# bela_expansion_card_3.net
KiCad netlist of a schematic drawn in Altium Designer
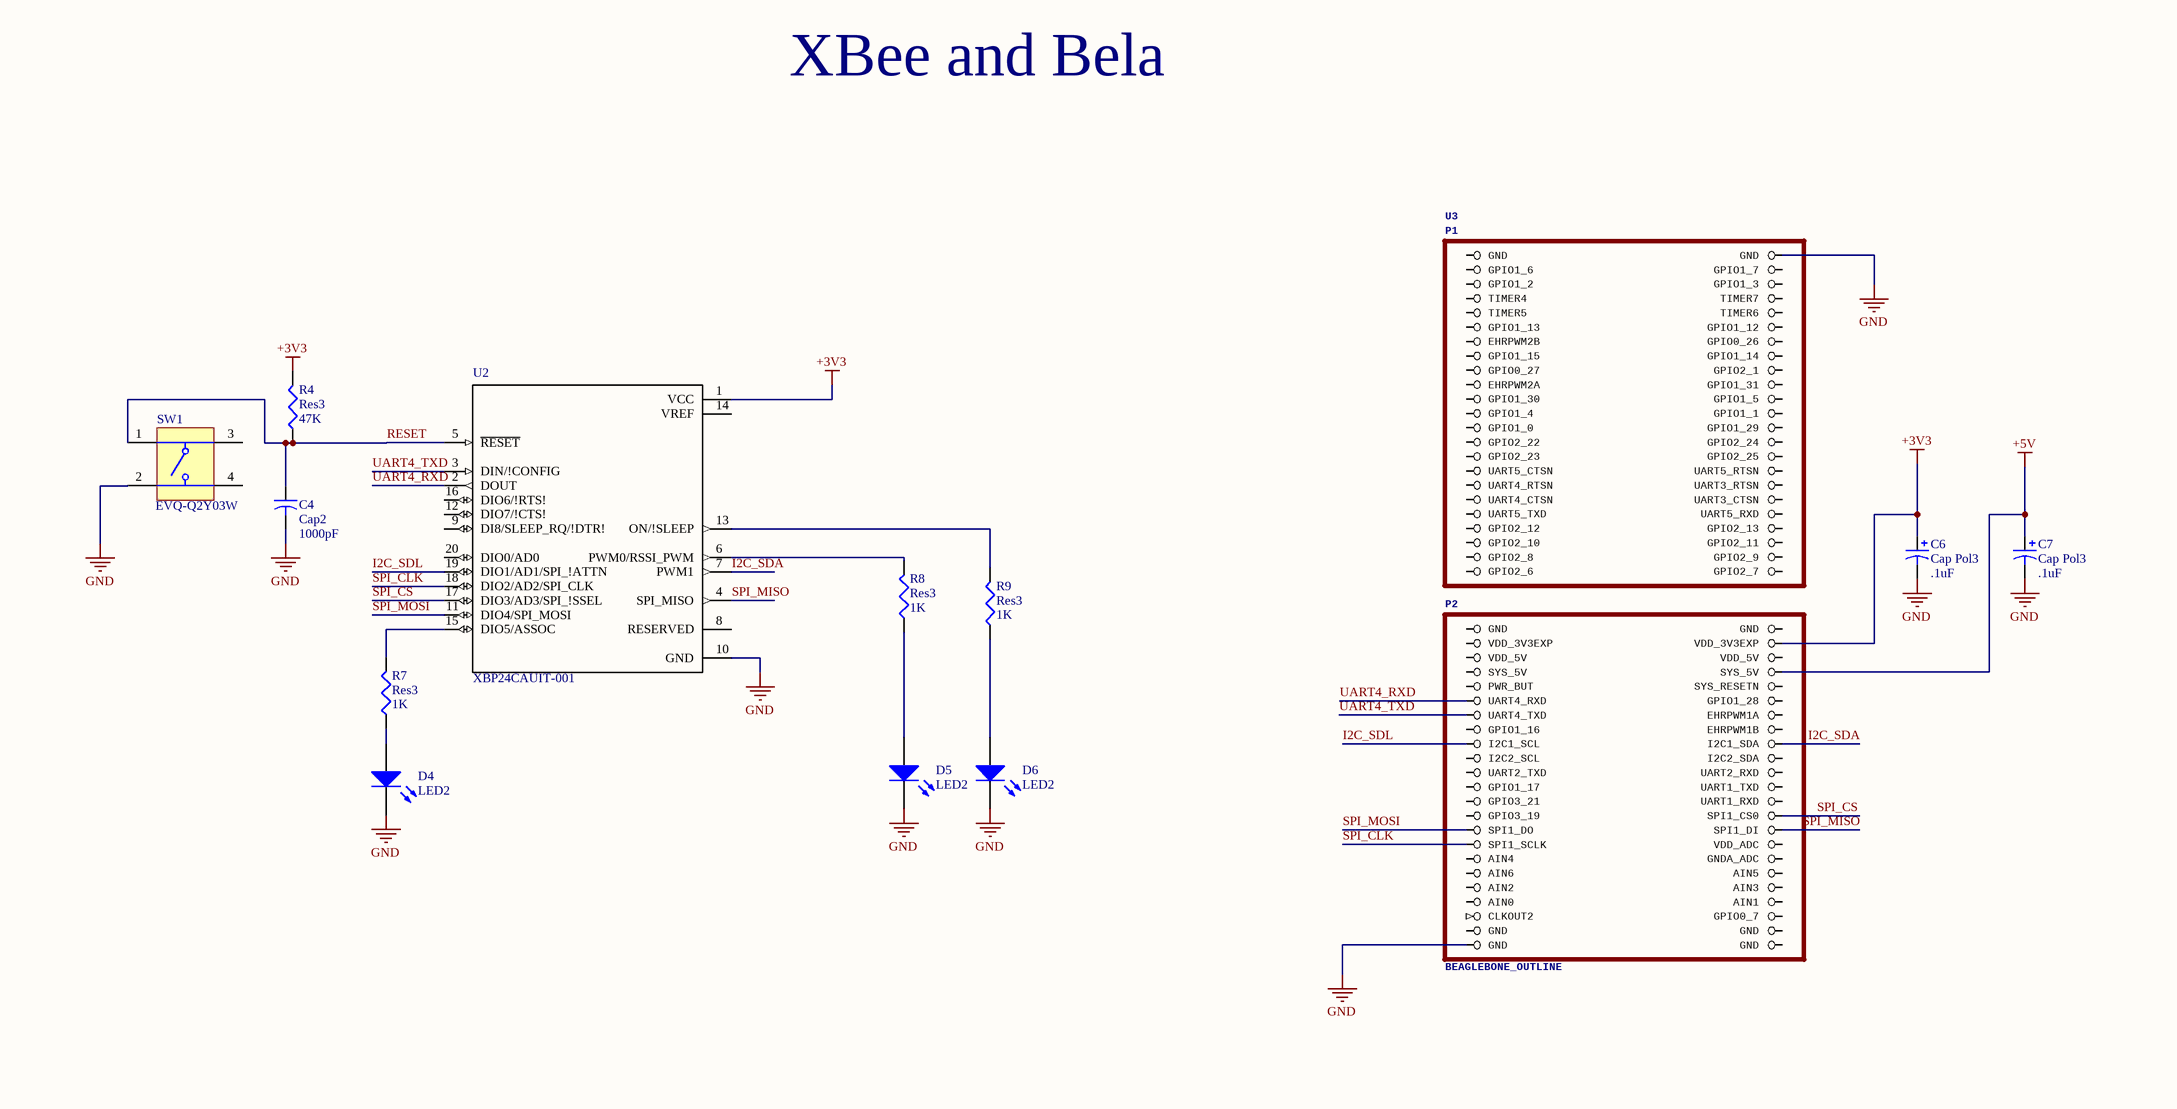
[diagram p0: bela_expansion_card_3.SchDoc]

(export (version "E")
  (design (tool "Eeschema 10.0.6"))
  (components
    (comp (ref "C4")
      (value "Cap2")
      (footprint "C0805")
      (description "Capacitor")
      (fields (field (name "ALTIUM_VALUE") "1000pF") (field (name "PUBLISHER") "Altium Limited"))
      (libsource (lib "EE_Emerge_SkillsProject") (part "Cap2_4"))
    )
    (comp (ref "C6")
      (value "Cap Pol3")
      (footprint "C0805")
      (description "Polarized Capacitor (Surface Mount)")
      (fields (field (name "ALTIUM_VALUE") ".1uF") (field (name "PUBLISHER") "Altium Limited"))
      (libsource (lib "Miscellaneous Devices") (part "Cap Pol3"))
    )
    (comp (ref "C7")
      (value "Cap Pol3")
      (footprint "C0805")
      (description "Polarized Capacitor (Surface Mount)")
      (fields (field (name "ALTIUM_VALUE") ".1uF") (field (name "PUBLISHER") "Altium Limited"))
      (libsource (lib "Miscellaneous Devices") (part "Cap Pol3"))
    )
    (comp (ref "D4")
      (value "LED2")
      (footprint "3.2X1.6X1.1")
      (description "Typical RED, GREEN, YELLOW, AMBER GaAs LED")
      (fields (field (name "PUBLISHER") "Altium Limited"))
      (libsource (lib "Miscellaneous Devices") (part "LED2"))
    )
    (comp (ref "D5")
      (value "LED2")
      (footprint "3.2X1.6X1.1")
      (description "Typical RED, GREEN, YELLOW, AMBER GaAs LED")
      (fields (field (name "PUBLISHER") "Altium Limited"))
      (libsource (lib "Miscellaneous Devices") (part "LED2"))
    )
    (comp (ref "D6")
      (value "LED2")
      (footprint "3.2X1.6X1.1")
      (description "Typical RED, GREEN, YELLOW, AMBER GaAs LED")
      (fields (field (name "PUBLISHER") "Altium Limited"))
      (libsource (lib "Miscellaneous Devices") (part "LED2"))
    )
    (comp (ref "R4")
      (value "Res3")
      (footprint "6-0805_L")
      (description "Resistor")
      (fields (field (name "ALTIUM_VALUE") "47K") (field (name "PUBLISHER") "Altium Limited"))
      (libsource (lib "Miscellaneous Devices") (part "Res3"))
    )
    (comp (ref "R7")
      (value "Res3")
      (footprint "6-0805_L")
      (description "Resistor")
      (fields (field (name "ALTIUM_VALUE") "1K") (field (name "PUBLISHER") "Altium Limited"))
      (libsource (lib "Miscellaneous Devices") (part "Res3"))
    )
    (comp (ref "R8")
      (value "Res3")
      (footprint "6-0805_L")
      (description "Resistor")
      (fields (field (name "ALTIUM_VALUE") "1K") (field (name "PUBLISHER") "Altium Limited"))
      (libsource (lib "Miscellaneous Devices") (part "Res3"))
    )
    (comp (ref "R9")
      (value "Res3")
      (footprint "6-0805_L")
      (description "Resistor")
      (fields (field (name "ALTIUM_VALUE") "1K") (field (name "PUBLISHER") "Altium Limited"))
      (libsource (lib "Miscellaneous Devices") (part "Res3"))
    )
    (comp (ref "SW1")
      (value "EVQ-Q2Y03W")
      (footprint "PNSC-EVQQ2_V")
      (description "Light Touch Switche, 3.5 N Force, Height 3.1 mm, -40 to 85 degC, 4-Pin SMD, RoHS, Tape and Reel")
      (fields (field (name "MANUFACTURER") "Panasonic"))
      (libsource (lib "Altium Content Vault") (part "SW-SPST-4"))
    )
    (comp (ref "U2")
      (value "XBP24CAUIT-001")
      (footprint "*MODULE_XBP24CAUIT-001")
      (description "802.15.4 Transceiver Module 2.4GHz Antenna Not Included, U.FL Through Hole")
      (fields (field (name "MF") "Digi International"))
      (libsource (lib "XBP24CAUIT-001") (part "XBP24CAUIT-001"))
    )
    (comp (ref "U3")
      (value "BEAGLEBONE_OUTLINE")
      (footprint "BEAGLEBONE_SHIELD")
      (description "Should match A3 pinout - but not completely tested")
      (fields (field (name "P1") "P1") (field (name "P2") "P2"))
      (libsource (lib "adafruit") (part "BEAGLEBONE_OUTLINE"))
    )
  )
  (nets
    (net (code "1") (name "+3V3") (class "Default")
      (node (ref "C6") (pin "1") (pinfunction "1_1") (pintype "passive"))
      (node (ref "R4") (pin "2") (pinfunction "2_2") (pintype "passive"))
      (node (ref "U2") (pin "1") (pinfunction "VCC_1") (pintype "power_in"))
      (node (ref "U3") (pin "50") (pinfunction "VDD_3V3EXP_50") (pintype "power_in"))
    )
    (net (code "2") (name "+5V") (class "Default")
      (node (ref "C7") (pin "1") (pinfunction "1_1") (pintype "passive"))
      (node (ref "U3") (pin "54") (pinfunction "SYS_5V_54") (pintype "passive"))
    )
    (net (code "3") (name "/I2C_SDA") (class "Default")
      (node (ref "U2") (pin "7") (pinfunction "PWM1_7") (pintype "output"))
      (node (ref "U3") (pin "64") (pinfunction "I2C1_SDA_64") (pintype "passive"))
    )
    (net (code "4") (name "/I2C_SDL") (class "Default")
      (node (ref "U2") (pin "19") (pinfunction "DIO1/AD1/SPI_!ATTN_19") (pintype "bidirectional"))
      (node (ref "U3") (pin "63") (pinfunction "I2C1_SCL_63") (pintype "passive"))
    )
    (net (code "5") (name "/RESET") (class "Default")
      (node (ref "C4") (pin "1") (pinfunction "1_1") (pintype "passive"))
      (node (ref "R4") (pin "1") (pinfunction "1_1") (pintype "passive"))
      (node (ref "SW1") (pin "1") (pinfunction "A_1") (pintype "passive"))
      (node (ref "U2") (pin "5") (pinfunction "~{RESET}_5") (pintype "input"))
    )
    (net (code "6") (name "/SPI_CLK") (class "Default")
      (node (ref "U2") (pin "18") (pinfunction "DIO2/AD2/SPI_CLK_18") (pintype "bidirectional"))
      (node (ref "U3") (pin "77") (pinfunction "SPI1_SCLK_77") (pintype "passive"))
    )
    (net (code "7") (name "/SPI_CS") (class "Default")
      (node (ref "U2") (pin "17") (pinfunction "DIO3/AD3/SPI_!SSEL_17") (pintype "bidirectional"))
      (node (ref "U3") (pin "74") (pinfunction "SPI1_CS0_74") (pintype "passive"))
    )
    (net (code "8") (name "/SPI_MISO") (class "Default")
      (node (ref "U2") (pin "4") (pinfunction "SPI_MISO_4") (pintype "output"))
      (node (ref "U3") (pin "76") (pinfunction "SPI1_DI_76") (pintype "passive"))
    )
    (net (code "9") (name "/SPI_MOSI") (class "Default")
      (node (ref "U2") (pin "11") (pinfunction "DIO4/SPI_MOSI_11") (pintype "bidirectional"))
      (node (ref "U3") (pin "75") (pinfunction "SPI1_DO_75") (pintype "passive"))
    )
    (net (code "10") (name "/UART4_RXD") (class "Default")
      (node (ref "U2") (pin "2") (pinfunction "DOUT_2") (pintype "output"))
      (node (ref "U3") (pin "57") (pinfunction "UART4_RXD_57") (pintype "passive"))
    )
    (net (code "11") (name "/UART4_TXD") (class "Default")
      (node (ref "U2") (pin "3") (pinfunction "DIN/!CONFIG_3") (pintype "input"))
      (node (ref "U3") (pin "59") (pinfunction "UART4_TXD_59") (pintype "passive"))
    )
    (net (code "12") (name "GND") (class "Default")
      (node (ref "C4") (pin "2") (pinfunction "2_2") (pintype "passive"))
      (node (ref "C6") (pin "2") (pinfunction "2_2") (pintype "passive"))
      (node (ref "C7") (pin "2") (pinfunction "2_2") (pintype "passive"))
      (node (ref "D4") (pin "2") (pinfunction "K_2") (pintype "passive"))
      (node (ref "D5") (pin "2") (pinfunction "K_2") (pintype "passive"))
      (node (ref "D6") (pin "2") (pinfunction "K_2") (pintype "passive"))
      (node (ref "SW1") (pin "2") (pinfunction "B_2") (pintype "passive"))
      (node (ref "U2") (pin "10") (pinfunction "GND_10") (pintype "power_in"))
      (node (ref "U3") (pin "2") (pinfunction "GND_2") (pintype "power_in"))
      (node (ref "U3") (pin "91") (pinfunction "GND_91") (pintype "power_in"))
    )
    (net (code "13") (name "Net-(D4-A)") (class "Default")
      (node (ref "D4") (pin "1") (pinfunction "A_1") (pintype "passive"))
      (node (ref "R7") (pin "1") (pinfunction "1_1") (pintype "passive"))
    )
    (net (code "14") (name "Net-(D5-A)") (class "Default")
      (node (ref "D5") (pin "1") (pinfunction "A_1") (pintype "passive"))
      (node (ref "R8") (pin "1") (pinfunction "1_1") (pintype "passive"))
    )
    (net (code "15") (name "Net-(D6-A)") (class "Default")
      (node (ref "D6") (pin "1") (pinfunction "A_1") (pintype "passive"))
      (node (ref "R9") (pin "1") (pinfunction "1_1") (pintype "passive"))
    )
    (net (code "16") (name "Net-(U2-DIO5{slash}ASSOC)") (class "Default")
      (node (ref "R7") (pin "2") (pinfunction "2_2") (pintype "passive"))
      (node (ref "U2") (pin "15") (pinfunction "DIO5/ASSOC_15") (pintype "bidirectional"))
    )
    (net (code "17") (name "Net-(U2-ON{slash}!SLEEP)") (class "Default")
      (node (ref "R9") (pin "2") (pinfunction "2_2") (pintype "passive"))
      (node (ref "U2") (pin "13") (pinfunction "ON/!SLEEP_13") (pintype "output"))
    )
    (net (code "18") (name "Net-(U2-PWM0{slash}RSSI_PWM)") (class "Default")
      (node (ref "R8") (pin "2") (pinfunction "2_2") (pintype "passive"))
      (node (ref "U2") (pin "6") (pinfunction "PWM0/RSSI_PWM_6") (pintype "output"))
    )
    (net (code "19") (name "unconnected-(SW1-A'-Pad3)") (class "Default")
      (node (ref "SW1") (pin "3") (pinfunction "A'_3") (pintype "passive"))
    )
    (net (code "20") (name "unconnected-(SW1-B'-Pad4)") (class "Default")
      (node (ref "SW1") (pin "4") (pinfunction "B'_4") (pintype "passive"))
    )
    (net (code "21") (name "unconnected-(U2-DI8{slash}SLEEP_RQ{slash}!DTR!-Pad9)") (class "Default")
      (node (ref "U2") (pin "9") (pinfunction "DI8/SLEEP_RQ/!DTR!_9") (pintype "bidirectional"))
    )
    (net (code "22") (name "unconnected-(U2-DIO0{slash}AD0-Pad20)") (class "Default")
      (node (ref "U2") (pin "20") (pinfunction "DIO0/AD0_20") (pintype "bidirectional"))
    )
    (net (code "23") (name "unconnected-(U2-DIO6{slash}!RTS!-Pad16)") (class "Default")
      (node (ref "U2") (pin "16") (pinfunction "DIO6/!RTS!_16") (pintype "bidirectional"))
    )
    (net (code "24") (name "unconnected-(U2-DIO7{slash}!CTS!-Pad12)") (class "Default")
      (node (ref "U2") (pin "12") (pinfunction "DIO7/!CTS!_12") (pintype "bidirectional"))
    )
    (net (code "25") (name "unconnected-(U2-RESERVED-Pad8)") (class "Default")
      (node (ref "U2") (pin "8") (pinfunction "RESERVED_8") (pintype "passive"))
    )
    (net (code "26") (name "unconnected-(U2-VREF-Pad14)") (class "Default")
      (node (ref "U2") (pin "14") (pinfunction "VREF_14") (pintype "power_in"))
    )
    (net (code "27") (name "unconnected-(U3-AIN0-Pad85)") (class "Default")
      (node (ref "U3") (pin "85") (pinfunction "AIN0_85") (pintype "power_in"))
    )
    (net (code "28") (name "unconnected-(U3-AIN1-Pad86)") (class "Default")
      (node (ref "U3") (pin "86") (pinfunction "AIN1_86") (pintype "passive"))
    )
    (net (code "29") (name "unconnected-(U3-AIN2-Pad83)") (class "Default")
      (node (ref "U3") (pin "83") (pinfunction "AIN2_83") (pintype "passive"))
    )
    (net (code "30") (name "unconnected-(U3-AIN3-Pad84)") (class "Default")
      (node (ref "U3") (pin "84") (pinfunction "AIN3_84") (pintype "passive"))
    )
    (net (code "31") (name "unconnected-(U3-AIN4-Pad79)") (class "Default")
      (node (ref "U3") (pin "79") (pinfunction "AIN4_79") (pintype "passive"))
    )
    (net (code "32") (name "unconnected-(U3-AIN5-Pad82)") (class "Default")
      (node (ref "U3") (pin "82") (pinfunction "AIN5_82") (pintype "passive"))
    )
    (net (code "33") (name "unconnected-(U3-AIN6-Pad81)") (class "Default")
      (node (ref "U3") (pin "81") (pinfunction "AIN6_81") (pintype "passive"))
    )
    (net (code "34") (name "unconnected-(U3-CLKOUT2-Pad87)") (class "Default")
      (node (ref "U3") (pin "87") (pinfunction "CLKOUT2_87") (pintype "input"))
    )
    (net (code "35") (name "unconnected-(U3-EHRPWM1A-Pad60)") (class "Default")
      (node (ref "U3") (pin "60") (pinfunction "EHRPWM1A_60") (pintype "passive"))
    )
    (net (code "36") (name "unconnected-(U3-EHRPWM1B-Pad62)") (class "Default")
      (node (ref "U3") (pin "62") (pinfunction "EHRPWM1B_62") (pintype "passive"))
    )
    (net (code "37") (name "unconnected-(U3-EHRPWM2A-Pad19)") (class "Default")
      (node (ref "U3") (pin "19") (pinfunction "EHRPWM2A_19") (pintype "passive"))
    )
    (net (code "38") (name "unconnected-(U3-EHRPWM2B-Pad13)") (class "Default")
      (node (ref "U3") (pin "13") (pinfunction "EHRPWM2B_13") (pintype "passive"))
    )
    (net (code "39") (name "unconnected-(U3-GND-Pad1)") (class "Default")
      (node (ref "U3") (pin "1") (pinfunction "GND_1") (pintype "power_in"))
    )
    (net (code "40") (name "unconnected-(U3-GND-Pad47)") (class "Default")
      (node (ref "U3") (pin "47") (pinfunction "GND_47") (pintype "power_in"))
    )
    (net (code "41") (name "unconnected-(U3-GND-Pad48)") (class "Default")
      (node (ref "U3") (pin "48") (pinfunction "GND_48") (pintype "power_in"))
    )
    (net (code "42") (name "unconnected-(U3-GND-Pad89)") (class "Default")
      (node (ref "U3") (pin "89") (pinfunction "GND_89") (pintype "power_in"))
    )
    (net (code "43") (name "unconnected-(U3-GND-Pad90)") (class "Default")
      (node (ref "U3") (pin "90") (pinfunction "GND_90") (pintype "power_in"))
    )
    (net (code "44") (name "unconnected-(U3-GND-Pad92)") (class "Default")
      (node (ref "U3") (pin "92") (pinfunction "GND_92") (pintype "power_in"))
    )
    (net (code "45") (name "unconnected-(U3-GNDA_ADC-Pad80)") (class "Default")
      (node (ref "U3") (pin "80") (pinfunction "GNDA_ADC_80") (pintype "passive"))
    )
    (net (code "46") (name "unconnected-(U3-GPIO0_7-Pad88)") (class "Default")
      (node (ref "U3") (pin "88") (pinfunction "GPIO0_7_88") (pintype "passive"))
    )
    (net (code "47") (name "unconnected-(U3-GPIO0_26-Pad14)") (class "Default")
      (node (ref "U3") (pin "14") (pinfunction "GPIO0_26_14") (pintype "passive"))
    )
    (net (code "48") (name "unconnected-(U3-GPIO0_27-Pad17)") (class "Default")
      (node (ref "U3") (pin "17") (pinfunction "GPIO0_27_17") (pintype "passive"))
    )
    (net (code "49") (name "unconnected-(U3-GPIO1_0-Pad25)") (class "Default")
      (node (ref "U3") (pin "25") (pinfunction "GPIO1_0_25") (pintype "passive"))
    )
    (net (code "50") (name "unconnected-(U3-GPIO1_1-Pad24)") (class "Default")
      (node (ref "U3") (pin "24") (pinfunction "GPIO1_1_24") (pintype "passive"))
    )
    (net (code "51") (name "unconnected-(U3-GPIO1_2-Pad5)") (class "Default")
      (node (ref "U3") (pin "5") (pinfunction "GPIO1_2_5") (pintype "passive"))
    )
    (net (code "52") (name "unconnected-(U3-GPIO1_3-Pad6)") (class "Default")
      (node (ref "U3") (pin "6") (pinfunction "GPIO1_3_6") (pintype "passive"))
    )
    (net (code "53") (name "unconnected-(U3-GPIO1_4-Pad23)") (class "Default")
      (node (ref "U3") (pin "23") (pinfunction "GPIO1_4_23") (pintype "passive"))
    )
    (net (code "54") (name "unconnected-(U3-GPIO1_5-Pad22)") (class "Default")
      (node (ref "U3") (pin "22") (pinfunction "GPIO1_5_22") (pintype "passive"))
    )
    (net (code "55") (name "unconnected-(U3-GPIO1_6-Pad3)") (class "Default")
      (node (ref "U3") (pin "3") (pinfunction "GPIO1_6_3") (pintype "passive"))
    )
    (net (code "56") (name "unconnected-(U3-GPIO1_7-Pad4)") (class "Default")
      (node (ref "U3") (pin "4") (pinfunction "GPIO1_7_4") (pintype "passive"))
    )
    (net (code "57") (name "unconnected-(U3-GPIO1_12-Pad12)") (class "Default")
      (node (ref "U3") (pin "12") (pinfunction "GPIO1_12_12") (pintype "passive"))
    )
    (net (code "58") (name "unconnected-(U3-GPIO1_13-Pad11)") (class "Default")
      (node (ref "U3") (pin "11") (pinfunction "GPIO1_13_11") (pintype "passive"))
    )
    (net (code "59") (name "unconnected-(U3-GPIO1_14-Pad16)") (class "Default")
      (node (ref "U3") (pin "16") (pinfunction "GPIO1_14_16") (pintype "passive"))
    )
    (net (code "60") (name "unconnected-(U3-GPIO1_15-Pad15)") (class "Default")
      (node (ref "U3") (pin "15") (pinfunction "GPIO1_15_15") (pintype "passive"))
    )
    (net (code "61") (name "unconnected-(U3-GPIO1_16-Pad61)") (class "Default")
      (node (ref "U3") (pin "61") (pinfunction "GPIO1_16_61") (pintype "passive"))
    )
    (net (code "62") (name "unconnected-(U3-GPIO1_17-Pad69)") (class "Default")
      (node (ref "U3") (pin "69") (pinfunction "GPIO1_17_69") (pintype "passive"))
    )
    (net (code "63") (name "unconnected-(U3-GPIO1_28-Pad58)") (class "Default")
      (node (ref "U3") (pin "58") (pinfunction "GPIO1_28_58") (pintype "passive"))
    )
    (net (code "64") (name "unconnected-(U3-GPIO1_29-Pad26)") (class "Default")
      (node (ref "U3") (pin "26") (pinfunction "GPIO1_29_26") (pintype "passive"))
    )
    (net (code "65") (name "unconnected-(U3-GPIO1_30-Pad21)") (class "Default")
      (node (ref "U3") (pin "21") (pinfunction "GPIO1_30_21") (pintype "passive"))
    )
    (net (code "66") (name "unconnected-(U3-GPIO1_31-Pad20)") (class "Default")
      (node (ref "U3") (pin "20") (pinfunction "GPIO1_31_20") (pintype "passive"))
    )
    (net (code "67") (name "unconnected-(U3-GPIO2_1-Pad18)") (class "Default")
      (node (ref "U3") (pin "18") (pinfunction "GPIO2_1_18") (pintype "passive"))
    )
    (net (code "68") (name "unconnected-(U3-GPIO2_6-Pad45)") (class "Default")
      (node (ref "U3") (pin "45") (pinfunction "GPIO2_6_45") (pintype "passive"))
    )
    (net (code "69") (name "unconnected-(U3-GPIO2_7-Pad46)") (class "Default")
      (node (ref "U3") (pin "46") (pinfunction "GPIO2_7_46") (pintype "passive"))
    )
    (net (code "70") (name "unconnected-(U3-GPIO2_8-Pad43)") (class "Default")
      (node (ref "U3") (pin "43") (pinfunction "GPIO2_8_43") (pintype "passive"))
    )
    (net (code "71") (name "unconnected-(U3-GPIO2_9-Pad44)") (class "Default")
      (node (ref "U3") (pin "44") (pinfunction "GPIO2_9_44") (pintype "passive"))
    )
    (net (code "72") (name "unconnected-(U3-GPIO2_10-Pad41)") (class "Default")
      (node (ref "U3") (pin "41") (pinfunction "GPIO2_10_41") (pintype "passive"))
    )
    (net (code "73") (name "unconnected-(U3-GPIO2_11-Pad42)") (class "Default")
      (node (ref "U3") (pin "42") (pinfunction "GPIO2_11_42") (pintype "passive"))
    )
    (net (code "74") (name "unconnected-(U3-GPIO2_12-Pad39)") (class "Default")
      (node (ref "U3") (pin "39") (pinfunction "GPIO2_12_39") (pintype "passive"))
    )
    (net (code "75") (name "unconnected-(U3-GPIO2_13-Pad40)") (class "Default")
      (node (ref "U3") (pin "40") (pinfunction "GPIO2_13_40") (pintype "passive"))
    )
    (net (code "76") (name "unconnected-(U3-GPIO2_22-Pad27)") (class "Default")
      (node (ref "U3") (pin "27") (pinfunction "GPIO2_22_27") (pintype "passive"))
    )
    (net (code "77") (name "unconnected-(U3-GPIO2_23-Pad29)") (class "Default")
      (node (ref "U3") (pin "29") (pinfunction "GPIO2_23_29") (pintype "passive"))
    )
    (net (code "78") (name "unconnected-(U3-GPIO2_24-Pad28)") (class "Default")
      (node (ref "U3") (pin "28") (pinfunction "GPIO2_24_28") (pintype "passive"))
    )
    (net (code "79") (name "unconnected-(U3-GPIO2_25-Pad30)") (class "Default")
      (node (ref "U3") (pin "30") (pinfunction "GPIO2_25_30") (pintype "passive"))
    )
    (net (code "80") (name "unconnected-(U3-GPIO3_19-Pad73)") (class "Default")
      (node (ref "U3") (pin "73") (pinfunction "GPIO3_19_73") (pintype "passive"))
    )
    (net (code "81") (name "unconnected-(U3-GPIO3_21-Pad71)") (class "Default")
      (node (ref "U3") (pin "71") (pinfunction "GPIO3_21_71") (pintype "passive"))
    )
    (net (code "82") (name "unconnected-(U3-I2C2_SCL-Pad65)") (class "Default")
      (node (ref "U3") (pin "65") (pinfunction "I2C2_SCL_65") (pintype "passive"))
    )
    (net (code "83") (name "unconnected-(U3-I2C2_SDA-Pad66)") (class "Default")
      (node (ref "U3") (pin "66") (pinfunction "I2C2_SDA_66") (pintype "passive"))
    )
    (net (code "84") (name "unconnected-(U3-PWR_BUT-Pad55)") (class "Default")
      (node (ref "U3") (pin "55") (pinfunction "PWR_BUT_55") (pintype "passive"))
    )
    (net (code "85") (name "unconnected-(U3-SYS_5V-Pad53)") (class "Default")
      (node (ref "U3") (pin "53") (pinfunction "SYS_5V_53") (pintype "power_in"))
    )
    (net (code "86") (name "unconnected-(U3-SYS_RESETN-Pad56)") (class "Default")
      (node (ref "U3") (pin "56") (pinfunction "SYS_RESETN_56") (pintype "passive"))
    )
    (net (code "87") (name "unconnected-(U3-TIMER4-Pad7)") (class "Default")
      (node (ref "U3") (pin "7") (pinfunction "TIMER4_7") (pintype "passive"))
    )
    (net (code "88") (name "unconnected-(U3-TIMER5-Pad9)") (class "Default")
      (node (ref "U3") (pin "9") (pinfunction "TIMER5_9") (pintype "passive"))
    )
    (net (code "89") (name "unconnected-(U3-TIMER6-Pad10)") (class "Default")
      (node (ref "U3") (pin "10") (pinfunction "TIMER6_10") (pintype "passive"))
    )
    (net (code "90") (name "unconnected-(U3-TIMER7-Pad8)") (class "Default")
      (node (ref "U3") (pin "8") (pinfunction "TIMER7_8") (pintype "passive"))
    )
    (net (code "91") (name "unconnected-(U3-UART1_RXD-Pad72)") (class "Default")
      (node (ref "U3") (pin "72") (pinfunction "UART1_RXD_72") (pintype "passive"))
    )
    (net (code "92") (name "unconnected-(U3-UART1_TXD-Pad70)") (class "Default")
      (node (ref "U3") (pin "70") (pinfunction "UART1_TXD_70") (pintype "passive"))
    )
    (net (code "93") (name "unconnected-(U3-UART2_RXD-Pad68)") (class "Default")
      (node (ref "U3") (pin "68") (pinfunction "UART2_RXD_68") (pintype "passive"))
    )
    (net (code "94") (name "unconnected-(U3-UART2_TXD-Pad67)") (class "Default")
      (node (ref "U3") (pin "67") (pinfunction "UART2_TXD_67") (pintype "passive"))
    )
    (net (code "95") (name "unconnected-(U3-UART3_CTSN-Pad36)") (class "Default")
      (node (ref "U3") (pin "36") (pinfunction "UART3_CTSN_36") (pintype "passive"))
    )
    (net (code "96") (name "unconnected-(U3-UART3_RTSN-Pad34)") (class "Default")
      (node (ref "U3") (pin "34") (pinfunction "UART3_RTSN_34") (pintype "passive"))
    )
    (net (code "97") (name "unconnected-(U3-UART4_CTSN-Pad35)") (class "Default")
      (node (ref "U3") (pin "35") (pinfunction "UART4_CTSN_35") (pintype "passive"))
    )
    (net (code "98") (name "unconnected-(U3-UART4_RTSN-Pad33)") (class "Default")
      (node (ref "U3") (pin "33") (pinfunction "UART4_RTSN_33") (pintype "passive"))
    )
    (net (code "99") (name "unconnected-(U3-UART5_CTSN-Pad31)") (class "Default")
      (node (ref "U3") (pin "31") (pinfunction "UART5_CTSN_31") (pintype "passive"))
    )
    (net (code "100") (name "unconnected-(U3-UART5_RTSN-Pad32)") (class "Default")
      (node (ref "U3") (pin "32") (pinfunction "UART5_RTSN_32") (pintype "passive"))
    )
    (net (code "101") (name "unconnected-(U3-UART5_RXD-Pad38)") (class "Default")
      (node (ref "U3") (pin "38") (pinfunction "UART5_RXD_38") (pintype "passive"))
    )
    (net (code "102") (name "unconnected-(U3-UART5_TXD-Pad37)") (class "Default")
      (node (ref "U3") (pin "37") (pinfunction "UART5_TXD_37") (pintype "passive"))
    )
    (net (code "103") (name "unconnected-(U3-VDD_3V3EXP-Pad49)") (class "Default")
      (node (ref "U3") (pin "49") (pinfunction "VDD_3V3EXP_49") (pintype "power_in"))
    )
    (net (code "104") (name "unconnected-(U3-VDD_5V-Pad51)") (class "Default")
      (node (ref "U3") (pin "51") (pinfunction "VDD_5V_51") (pintype "power_in"))
    )
    (net (code "105") (name "unconnected-(U3-VDD_5V-Pad52)") (class "Default")
      (node (ref "U3") (pin "52") (pinfunction "VDD_5V_52") (pintype "power_in"))
    )
    (net (code "106") (name "unconnected-(U3-VDD_ADC-Pad78)") (class "Default")
      (node (ref "U3") (pin "78") (pinfunction "VDD_ADC_78") (pintype "passive"))
    )
  )
)
